# PCB_capolavoro.net
KiCad netlist of a schematic drawn in EasyEDA
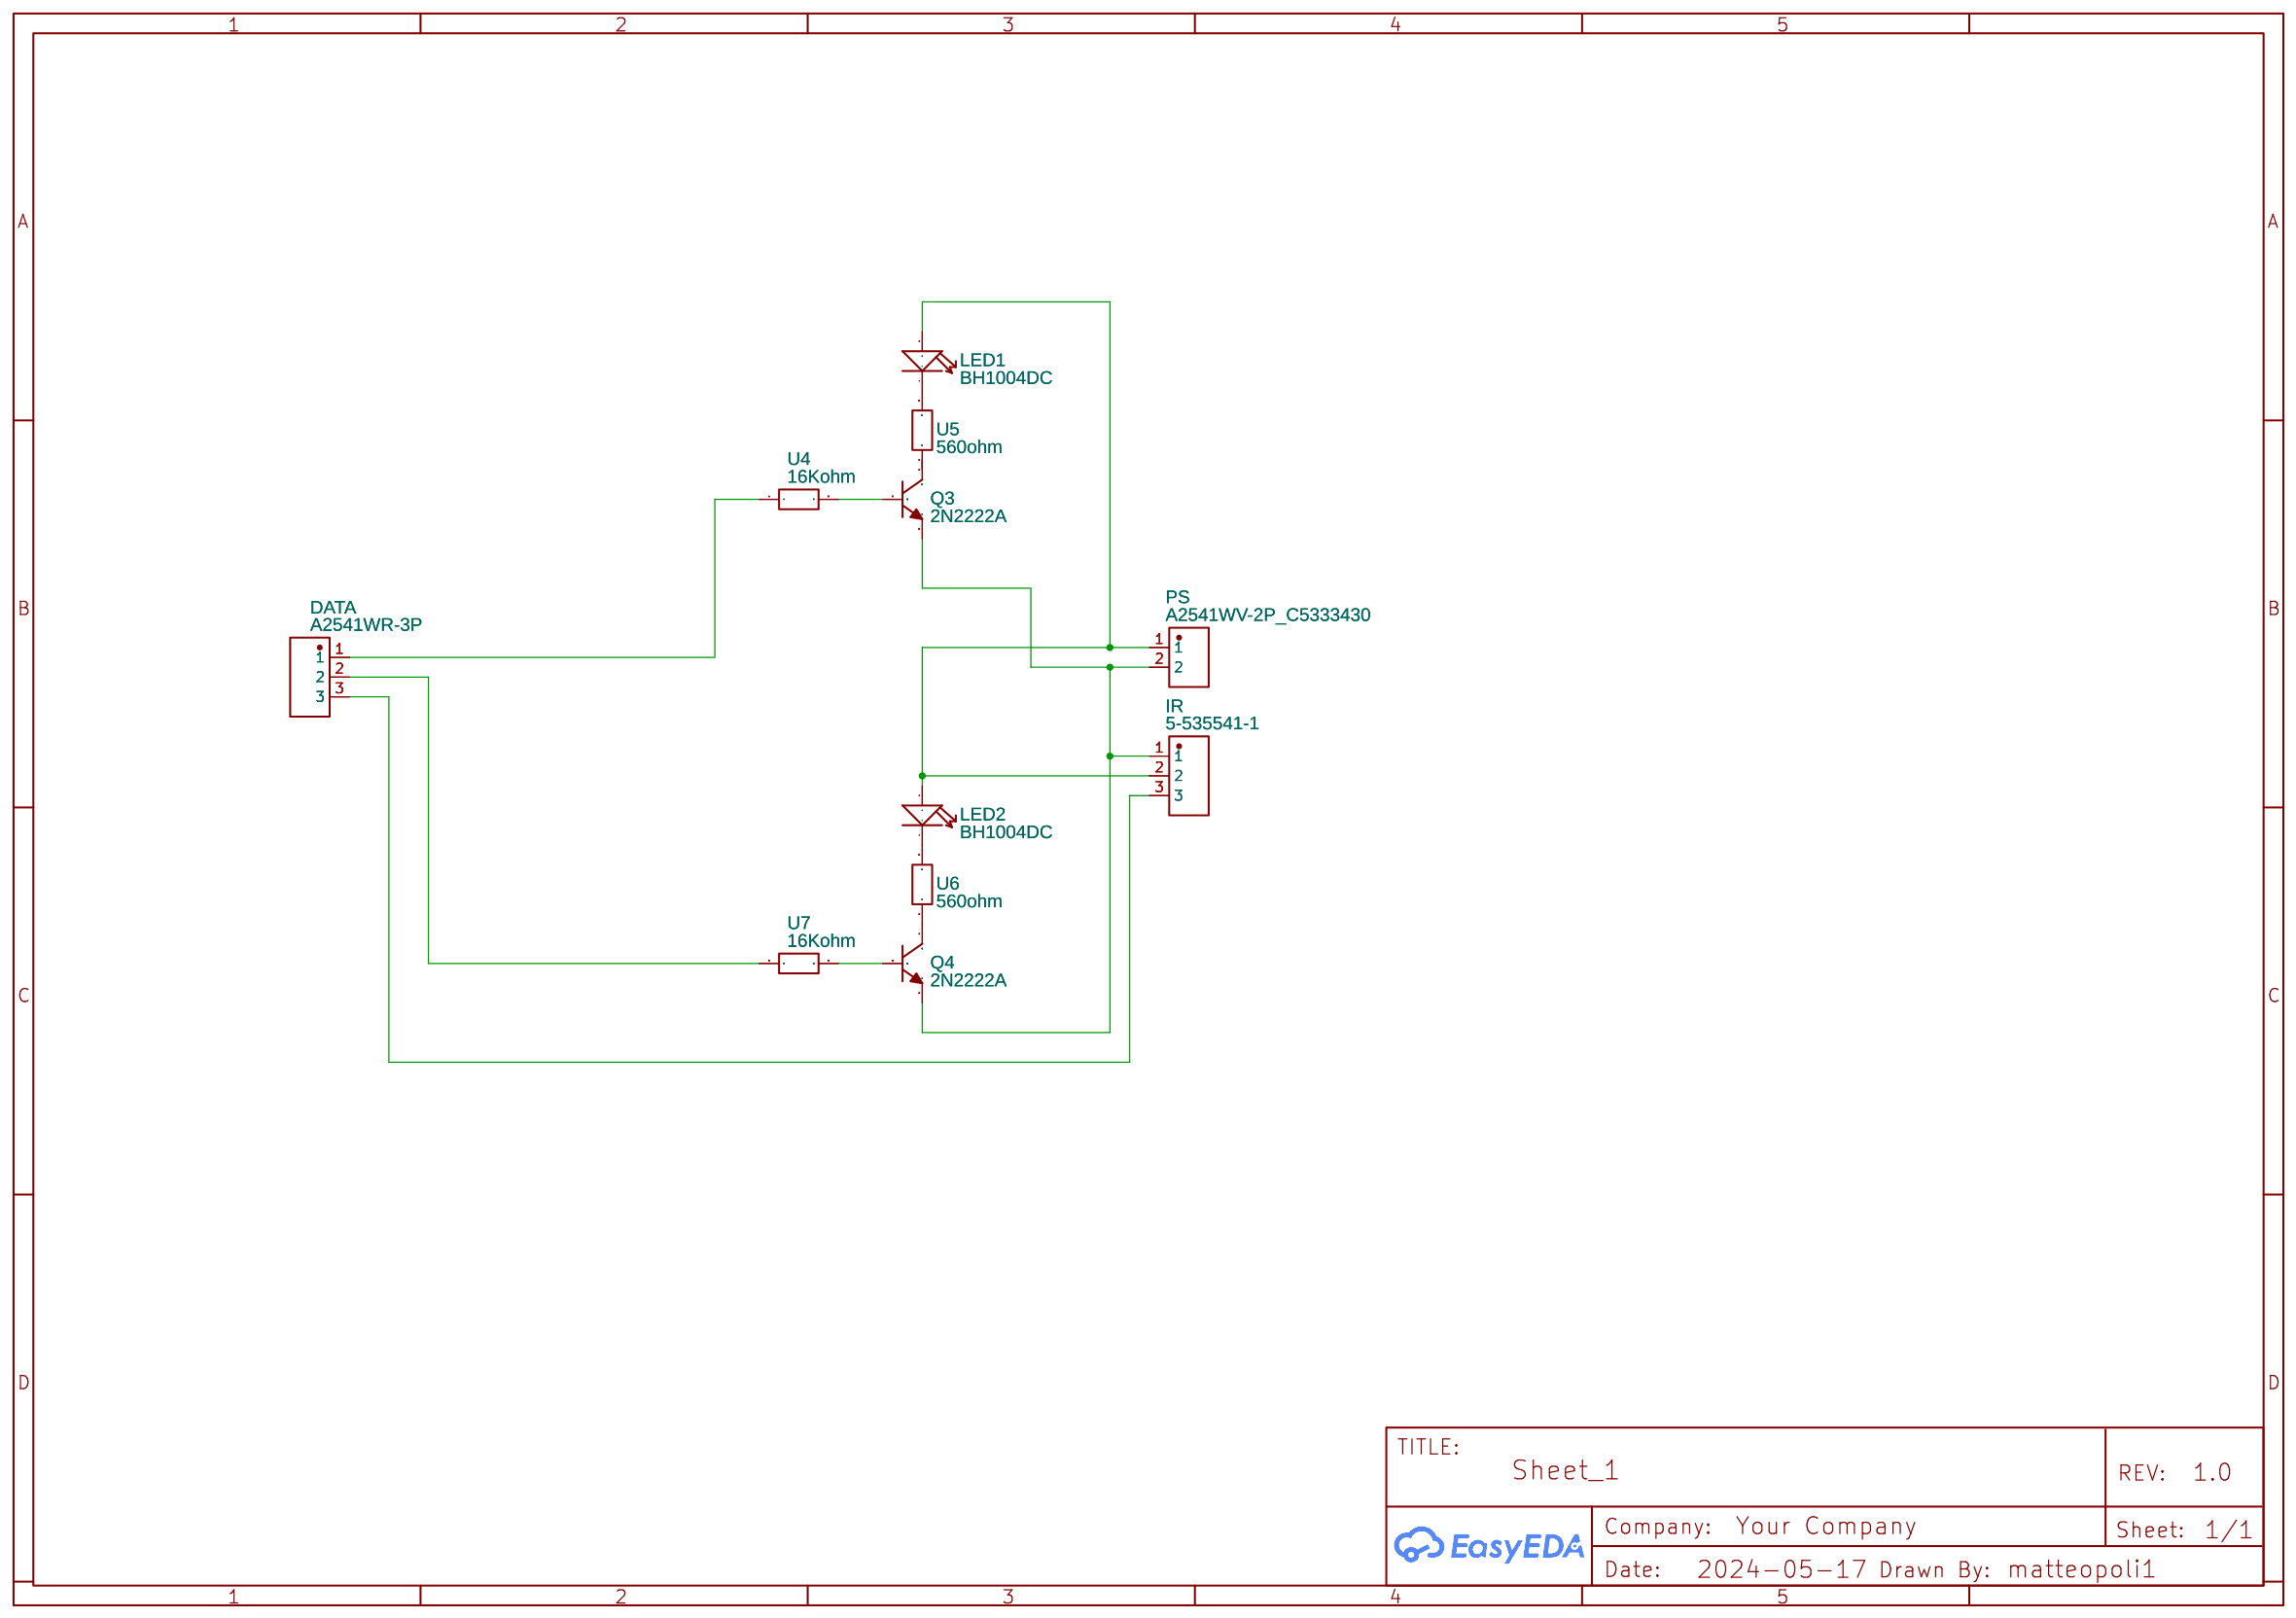
[diagram p0: schematic sheet]

(export (version "E")
  (design (tool "Eeschema 10.0.6"))
  (components
    (comp (ref "DATA")
      (value "A2541WR-3P")
      (fields (field (name "Manufacturer") "CJT(长江连接器)"))
      (libsource (lib "") (part "A2541WR-3P"))
    )
    (comp (ref "IR")
      (value "5-535541-1")
      (fields (field (name "Manufacturer") "TE Connectivity(泰科电子)"))
      (libsource (lib "") (part "5-535541-1"))
    )
    (comp (ref "LED1") (value "BH1004DC") (libsource (lib "") (part "BH1004DC")))
    (comp (ref "LED2") (value "BH1004DC") (libsource (lib "") (part "BH1004DC")))
    (comp (ref "PS")
      (value "A2541WV-2P_C5333430")
      (fields (field (name "Manufacturer Part") "A2541WV-2P") (field (name "Manufacturer") "CJT(长江连接器)"))
      (libsource (lib "") (part "A2541WV-2P_C5333430"))
    )
    (comp (ref "Q3")
      (value "2N2222A")
      (fields (field (name "Manufacturer") "BLUE ROCKET(蓝箭)"))
      (libsource (lib "") (part "2N2222A"))
    )
    (comp (ref "Q4")
      (value "2N2222A")
      (fields (field (name "Manufacturer") "BLUE ROCKET(蓝箭)"))
      (libsource (lib "") (part "2N2222A"))
    )
    (comp (ref "U4")
      (value "16Kohm")
      (fields (field (name "Manufacturer Part") "OF434JE") (field (name "Manufacturer") "Ohmite"))
      (libsource (lib "") (part "OF434JE_1"))
    )
    (comp (ref "U5")
      (value "560ohm")
      (fields (field (name "Manufacturer Part") "OF434JE") (field (name "Manufacturer") "Ohmite"))
      (libsource (lib "") (part "OF434JE"))
    )
    (comp (ref "U6")
      (value "560ohm")
      (fields (field (name "Manufacturer Part") "OF434JE") (field (name "Manufacturer") "Ohmite"))
      (libsource (lib "") (part "OF434JE"))
    )
    (comp (ref "U7")
      (value "16Kohm")
      (fields (field (name "Manufacturer Part") "OF434JE") (field (name "Manufacturer") "Ohmite"))
      (libsource (lib "") (part "OF434JE_1"))
    )
  )
  (nets
    (net (code "1") (name "Net-(DATA-Pad1)") (class "Default")
      (node (ref "DATA") (pin "1") (pinfunction "1_1") (pintype "unspecified"))
      (node (ref "U4") (pin "1") (pinfunction "1_1") (pintype "unspecified"))
    )
    (net (code "2") (name "Net-(DATA-Pad2)") (class "Default")
      (node (ref "DATA") (pin "2") (pinfunction "2_2") (pintype "unspecified"))
      (node (ref "U7") (pin "1") (pinfunction "1_1") (pintype "unspecified"))
    )
    (net (code "3") (name "Net-(DATA-Pad3)") (class "Default")
      (node (ref "DATA") (pin "3") (pinfunction "3_3") (pintype "unspecified"))
      (node (ref "IR") (pin "3") (pinfunction "3_3") (pintype "unspecified"))
    )
    (net (code "4") (name "Net-(IR-Pad2)") (class "Default")
      (node (ref "IR") (pin "2") (pinfunction "2_2") (pintype "unspecified"))
      (node (ref "LED1") (pin "+") (pinfunction "+_+") (pintype "unspecified"))
      (node (ref "LED2") (pin "+") (pinfunction "+_+") (pintype "unspecified"))
      (node (ref "PS") (pin "1") (pinfunction "1_1") (pintype "unspecified"))
    )
    (net (code "5") (name "Net-(LED1-Pad-)") (class "Default")
      (node (ref "LED1") (pin "-") (pinfunction "-_-") (pintype "unspecified"))
      (node (ref "U5") (pin "2") (pinfunction "2_2") (pintype "unspecified"))
    )
    (net (code "6") (name "Net-(LED2-Pad-)") (class "Default")
      (node (ref "LED2") (pin "-") (pinfunction "-_-") (pintype "unspecified"))
      (node (ref "U6") (pin "2") (pinfunction "2_2") (pintype "unspecified"))
    )
    (net (code "7") (name "Net-(Q3-B)") (class "Default")
      (node (ref "Q3") (pin "2") (pinfunction "B_2") (pintype "unspecified"))
      (node (ref "U4") (pin "2") (pinfunction "2_2") (pintype "unspecified"))
    )
    (net (code "8") (name "Net-(Q3-C)") (class "Default")
      (node (ref "Q3") (pin "1") (pinfunction "C_1") (pintype "unspecified"))
      (node (ref "U5") (pin "1") (pinfunction "1_1") (pintype "unspecified"))
    )
    (net (code "9") (name "Net-(Q3-E)") (class "Default")
      (node (ref "IR") (pin "1") (pinfunction "1_1") (pintype "unspecified"))
      (node (ref "PS") (pin "2") (pinfunction "2_2") (pintype "unspecified"))
      (node (ref "Q3") (pin "3") (pinfunction "E_3") (pintype "unspecified"))
      (node (ref "Q4") (pin "3") (pinfunction "E_3") (pintype "unspecified"))
    )
    (net (code "10") (name "Net-(Q4-B)") (class "Default")
      (node (ref "Q4") (pin "2") (pinfunction "B_2") (pintype "unspecified"))
      (node (ref "U7") (pin "2") (pinfunction "2_2") (pintype "unspecified"))
    )
    (net (code "11") (name "Net-(Q4-C)") (class "Default")
      (node (ref "Q4") (pin "1") (pinfunction "C_1") (pintype "unspecified"))
      (node (ref "U6") (pin "1") (pinfunction "1_1") (pintype "unspecified"))
    )
  )
)
